# INA219_design_block_buildin.net
KiCad netlist of a schematic drawn in EAGLE
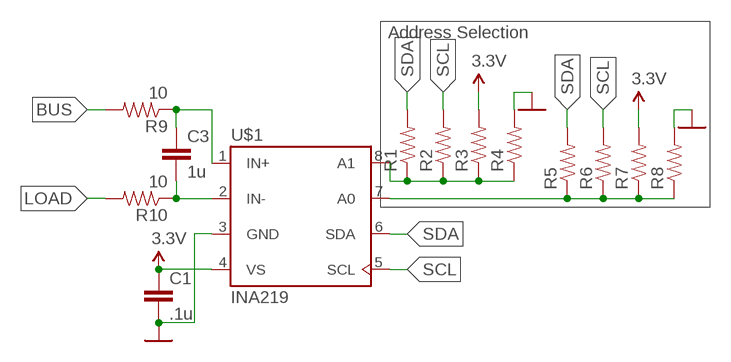
[diagram p0: schematic, sheet 1]

(export (version "E")
  (design (tool "Eeschema 10.0.6"))
  (components
    (comp (ref "C1")
      (value ".1u")
      (footprint "eagle-import:0805")
      (libsource (lib "eagle-import") (part "CAPACITOR0805"))
    )
    (comp (ref "C3")
      (value "1u")
      (footprint "eagle-import:0805")
      (libsource (lib "eagle-import") (part "CAPACITOR0805"))
    )
    (comp (ref "R1")
      (value "RESISTOR0805")
      (footprint "eagle-import:0805")
      (libsource (lib "eagle-import") (part "RESISTOR0805"))
    )
    (comp (ref "R2")
      (value "RESISTOR0805")
      (footprint "eagle-import:0805")
      (libsource (lib "eagle-import") (part "RESISTOR0805"))
    )
    (comp (ref "R3")
      (value "RESISTOR0805")
      (footprint "eagle-import:0805")
      (libsource (lib "eagle-import") (part "RESISTOR0805"))
    )
    (comp (ref "R4")
      (value "RESISTOR0805")
      (footprint "eagle-import:0805")
      (libsource (lib "eagle-import") (part "RESISTOR0805"))
    )
    (comp (ref "R5")
      (value "RESISTOR0805")
      (footprint "eagle-import:0805")
      (libsource (lib "eagle-import") (part "RESISTOR0805"))
    )
    (comp (ref "R6")
      (value "RESISTOR0805")
      (footprint "eagle-import:0805")
      (libsource (lib "eagle-import") (part "RESISTOR0805"))
    )
    (comp (ref "R7")
      (value "RESISTOR0805")
      (footprint "eagle-import:0805")
      (libsource (lib "eagle-import") (part "RESISTOR0805"))
    )
    (comp (ref "R8")
      (value "RESISTOR0805")
      (footprint "eagle-import:0805")
      (libsource (lib "eagle-import") (part "RESISTOR0805"))
    )
    (comp (ref "R9")
      (value "10")
      (footprint "eagle-import:0805")
      (libsource (lib "eagle-import") (part "RESISTOR0805"))
    )
    (comp (ref "R10")
      (value "10")
      (footprint "eagle-import:0805")
      (libsource (lib "eagle-import") (part "RESISTOR0805"))
    )
    (comp (ref "U$1")
      (value "INA219")
      (footprint "eagle-import:SOT-23-8")
      (libsource (lib "eagle-import") (part "INA219"))
    )
  )
  (nets
    (net (code "1") (name "3.3V") (class "Default")
      (node (ref "C1") (pin "1") (pinfunction "1_1") (pintype "passive"))
      (node (ref "R3") (pin "2") (pinfunction "2_2") (pintype "passive"))
      (node (ref "R7") (pin "2") (pinfunction "2_2") (pintype "passive"))
      (node (ref "U$1") (pin "4") (pinfunction "VS_4") (pintype "power_in"))
    )
    (net (code "2") (name "BUS") (class "Default")
      (node (ref "R9") (pin "2") (pinfunction "2_2") (pintype "passive"))
    )
    (net (code "3") (name "DGND") (class "Default")
      (node (ref "C1") (pin "2") (pinfunction "2_2") (pintype "passive"))
      (node (ref "R4") (pin "2") (pinfunction "2_2") (pintype "passive"))
      (node (ref "R8") (pin "2") (pinfunction "2_2") (pintype "passive"))
      (node (ref "U$1") (pin "3") (pinfunction "GND_3") (pintype "power_in"))
    )
    (net (code "4") (name "LOAD") (class "Default")
      (node (ref "R10") (pin "2") (pinfunction "2_2") (pintype "passive"))
    )
    (net (code "5") (name "Net-(U$1-A0)") (class "Default")
      (node (ref "R5") (pin "1") (pinfunction "1_1") (pintype "passive"))
      (node (ref "R6") (pin "1") (pinfunction "1_1") (pintype "passive"))
      (node (ref "R7") (pin "1") (pinfunction "1_1") (pintype "passive"))
      (node (ref "R8") (pin "1") (pinfunction "1_1") (pintype "passive"))
      (node (ref "U$1") (pin "7") (pinfunction "A0_7") (pintype "input"))
    )
    (net (code "6") (name "Net-(U$1-A1)") (class "Default")
      (node (ref "R1") (pin "1") (pinfunction "1_1") (pintype "passive"))
      (node (ref "R2") (pin "1") (pinfunction "1_1") (pintype "passive"))
      (node (ref "R3") (pin "1") (pinfunction "1_1") (pintype "passive"))
      (node (ref "R4") (pin "1") (pinfunction "1_1") (pintype "passive"))
      (node (ref "U$1") (pin "8") (pinfunction "A1_8") (pintype "input"))
    )
    (net (code "7") (name "Net-(U$1-IN+)") (class "Default")
      (node (ref "C3") (pin "1") (pinfunction "1_1") (pintype "passive"))
      (node (ref "R9") (pin "1") (pinfunction "1_1") (pintype "passive"))
      (node (ref "U$1") (pin "1") (pinfunction "IN+_1") (pintype "input"))
    )
    (net (code "8") (name "Net-(U$1-IN-)") (class "Default")
      (node (ref "C3") (pin "2") (pinfunction "2_2") (pintype "passive"))
      (node (ref "R10") (pin "1") (pinfunction "1_1") (pintype "passive"))
      (node (ref "U$1") (pin "2") (pinfunction "IN-_2") (pintype "input"))
    )
    (net (code "9") (name "SCL") (class "Default")
      (node (ref "R2") (pin "2") (pinfunction "2_2") (pintype "passive"))
      (node (ref "R6") (pin "2") (pinfunction "2_2") (pintype "passive"))
      (node (ref "U$1") (pin "5") (pinfunction "SCL_5") (pintype "input"))
    )
    (net (code "10") (name "SDA") (class "Default")
      (node (ref "R1") (pin "2") (pinfunction "2_2") (pintype "passive"))
      (node (ref "R5") (pin "2") (pinfunction "2_2") (pintype "passive"))
      (node (ref "U$1") (pin "6") (pinfunction "SDA_6") (pintype "output"))
    )
  )
)
